# LEDS3.net
KiCad netlist of a schematic drawn in Altium Designer
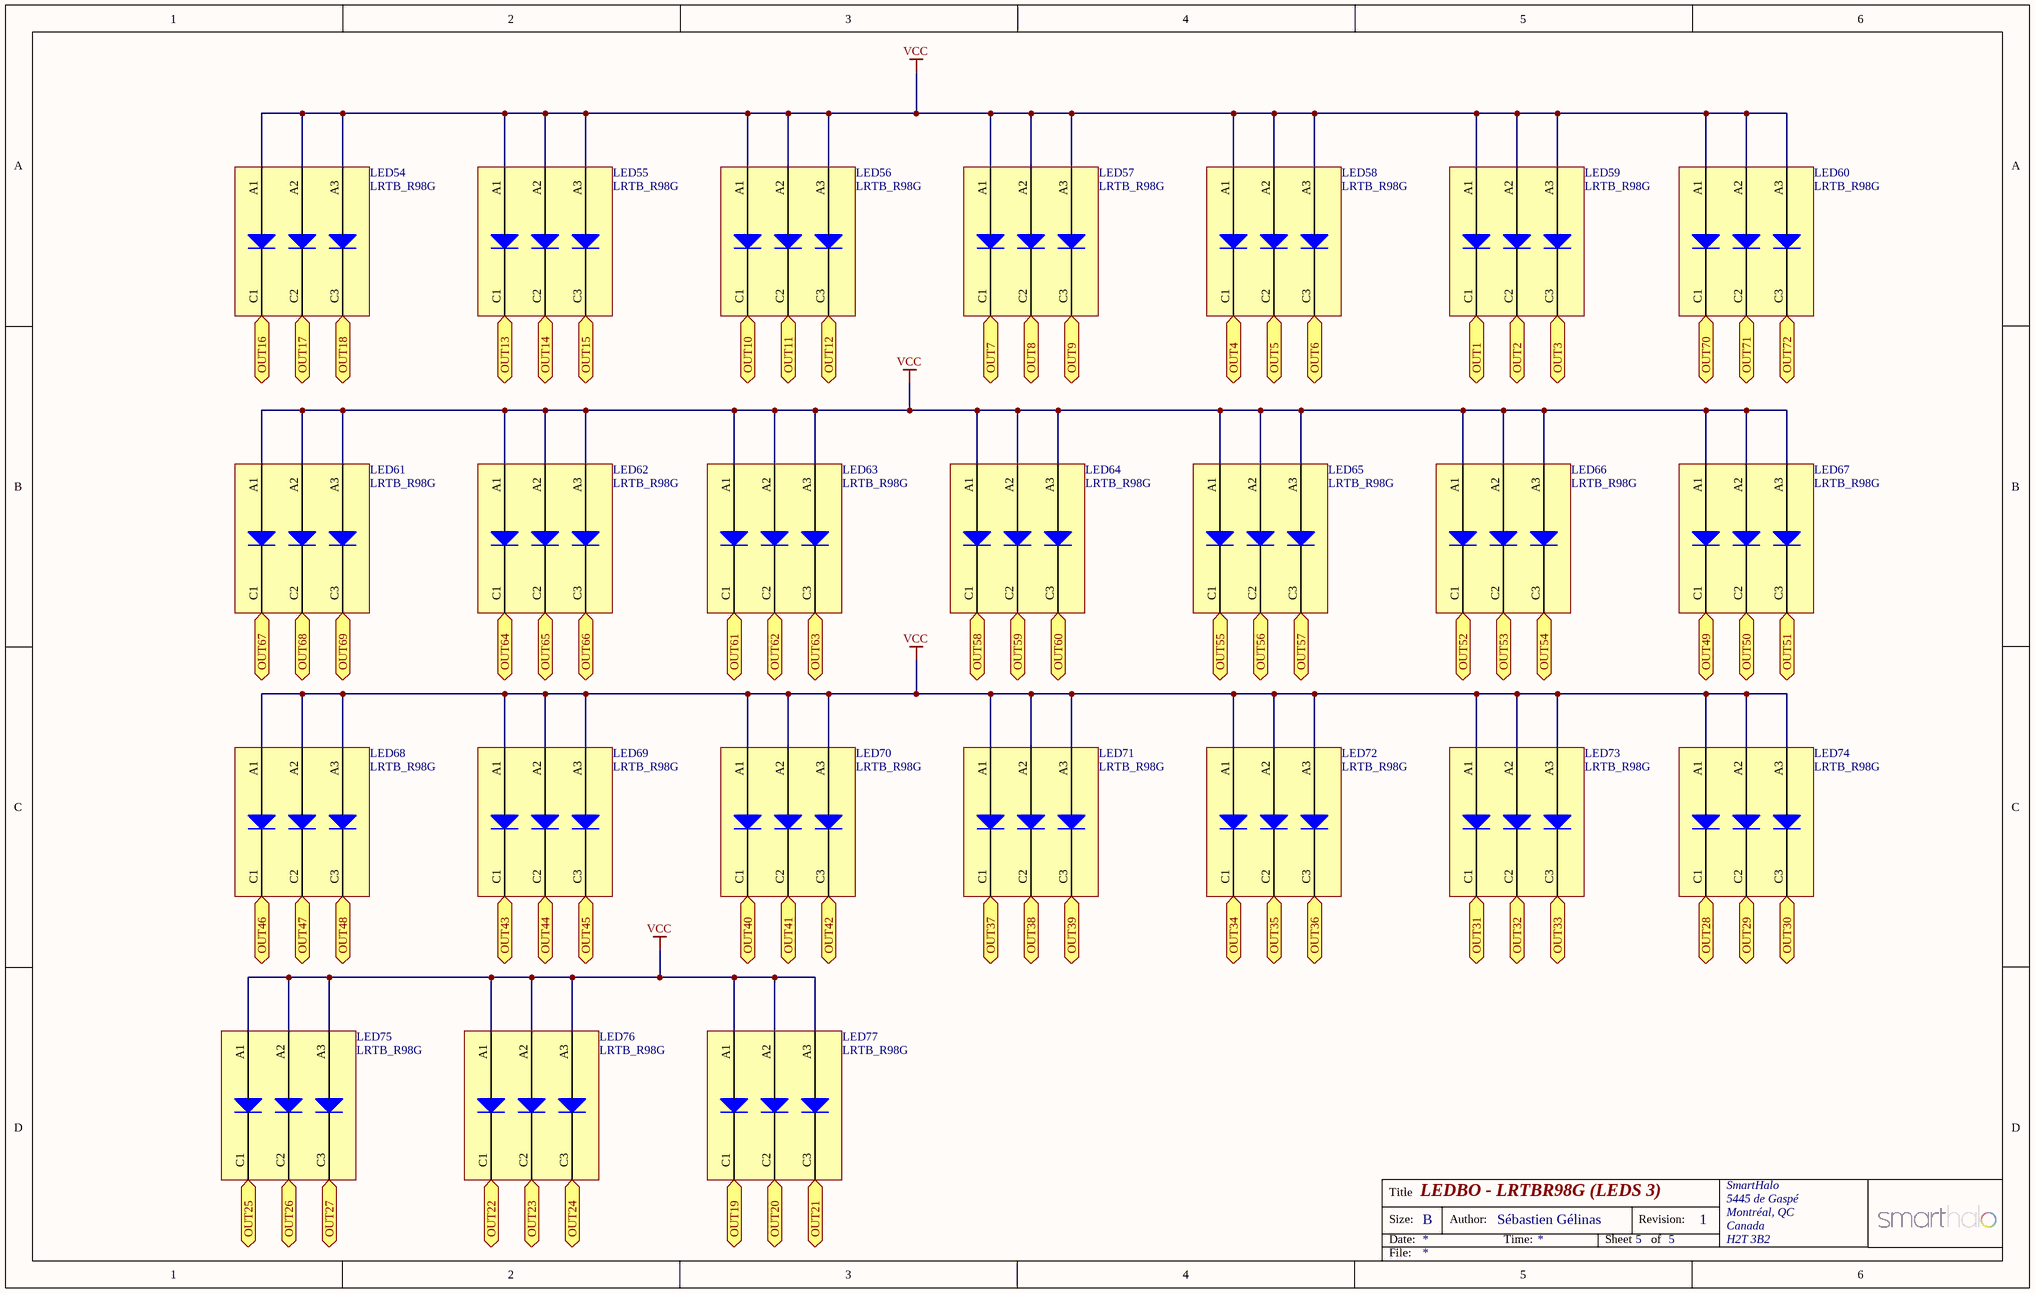
[diagram p0: LEDS3.SchDoc]

(export (version "E")
  (design (tool "Eeschema 10.0.6"))
  (components
    (comp (ref "LED54")
      (value "LRTB_R98G")
      (footprint "LRTB_R98G")
      (description "IC RGB LED OSRAM")
      (fields (field (name "MANUFACTURER") "OSRAM"))
      (libsource (lib "SmartHalo_Symbols") (part "LRTB_R98G"))
    )
    (comp (ref "LED55")
      (value "LRTB_R98G")
      (footprint "LRTB_R98G")
      (description "IC RGB LED OSRAM")
      (fields (field (name "MANUFACTURER") "OSRAM"))
      (libsource (lib "SmartHalo_Symbols") (part "LRTB_R98G"))
    )
    (comp (ref "LED56")
      (value "LRTB_R98G")
      (footprint "LRTB_R98G")
      (description "IC RGB LED OSRAM")
      (fields (field (name "MANUFACTURER") "OSRAM"))
      (libsource (lib "SmartHalo_Symbols") (part "LRTB_R98G"))
    )
    (comp (ref "LED57")
      (value "LRTB_R98G")
      (footprint "LRTB_R98G")
      (description "IC RGB LED OSRAM")
      (fields (field (name "MANUFACTURER") "OSRAM"))
      (libsource (lib "SmartHalo_Symbols") (part "LRTB_R98G"))
    )
    (comp (ref "LED58")
      (value "LRTB_R98G")
      (footprint "LRTB_R98G")
      (description "IC RGB LED OSRAM")
      (fields (field (name "MANUFACTURER") "OSRAM"))
      (libsource (lib "SmartHalo_Symbols") (part "LRTB_R98G"))
    )
    (comp (ref "LED59")
      (value "LRTB_R98G")
      (footprint "LRTB_R98G")
      (description "IC RGB LED OSRAM")
      (fields (field (name "MANUFACTURER") "OSRAM"))
      (libsource (lib "SmartHalo_Symbols") (part "LRTB_R98G"))
    )
    (comp (ref "LED60")
      (value "LRTB_R98G")
      (footprint "LRTB_R98G")
      (description "IC RGB LED OSRAM")
      (fields (field (name "MANUFACTURER") "OSRAM"))
      (libsource (lib "SmartHalo_Symbols") (part "LRTB_R98G"))
    )
    (comp (ref "LED61")
      (value "LRTB_R98G")
      (footprint "LRTB_R98G")
      (description "IC RGB LED OSRAM")
      (fields (field (name "MANUFACTURER") "OSRAM"))
      (libsource (lib "SmartHalo_Symbols") (part "LRTB_R98G"))
    )
    (comp (ref "LED62")
      (value "LRTB_R98G")
      (footprint "LRTB_R98G")
      (description "IC RGB LED OSRAM")
      (fields (field (name "MANUFACTURER") "OSRAM"))
      (libsource (lib "SmartHalo_Symbols") (part "LRTB_R98G"))
    )
    (comp (ref "LED63")
      (value "LRTB_R98G")
      (footprint "LRTB_R98G")
      (description "IC RGB LED OSRAM")
      (fields (field (name "MANUFACTURER") "OSRAM"))
      (libsource (lib "SmartHalo_Symbols") (part "LRTB_R98G"))
    )
    (comp (ref "LED64")
      (value "LRTB_R98G")
      (footprint "LRTB_R98G")
      (description "IC RGB LED OSRAM")
      (fields (field (name "MANUFACTURER") "OSRAM"))
      (libsource (lib "SmartHalo_Symbols") (part "LRTB_R98G"))
    )
    (comp (ref "LED65")
      (value "LRTB_R98G")
      (footprint "LRTB_R98G")
      (description "IC RGB LED OSRAM")
      (fields (field (name "MANUFACTURER") "OSRAM"))
      (libsource (lib "SmartHalo_Symbols") (part "LRTB_R98G"))
    )
    (comp (ref "LED66")
      (value "LRTB_R98G")
      (footprint "LRTB_R98G")
      (description "IC RGB LED OSRAM")
      (fields (field (name "MANUFACTURER") "OSRAM"))
      (libsource (lib "SmartHalo_Symbols") (part "LRTB_R98G"))
    )
    (comp (ref "LED67")
      (value "LRTB_R98G")
      (footprint "LRTB_R98G")
      (description "IC RGB LED OSRAM")
      (fields (field (name "MANUFACTURER") "OSRAM"))
      (libsource (lib "SmartHalo_Symbols") (part "LRTB_R98G"))
    )
    (comp (ref "LED68")
      (value "LRTB_R98G")
      (footprint "LRTB_R98G")
      (description "IC RGB LED OSRAM")
      (fields (field (name "MANUFACTURER") "OSRAM"))
      (libsource (lib "SmartHalo_Symbols") (part "LRTB_R98G"))
    )
    (comp (ref "LED69")
      (value "LRTB_R98G")
      (footprint "LRTB_R98G")
      (description "IC RGB LED OSRAM")
      (fields (field (name "MANUFACTURER") "OSRAM"))
      (libsource (lib "SmartHalo_Symbols") (part "LRTB_R98G"))
    )
    (comp (ref "LED70")
      (value "LRTB_R98G")
      (footprint "LRTB_R98G")
      (description "IC RGB LED OSRAM")
      (fields (field (name "MANUFACTURER") "OSRAM"))
      (libsource (lib "SmartHalo_Symbols") (part "LRTB_R98G"))
    )
    (comp (ref "LED71")
      (value "LRTB_R98G")
      (footprint "LRTB_R98G")
      (description "IC RGB LED OSRAM")
      (fields (field (name "MANUFACTURER") "OSRAM"))
      (libsource (lib "SmartHalo_Symbols") (part "LRTB_R98G"))
    )
    (comp (ref "LED72")
      (value "LRTB_R98G")
      (footprint "LRTB_R98G")
      (description "IC RGB LED OSRAM")
      (fields (field (name "MANUFACTURER") "OSRAM"))
      (libsource (lib "SmartHalo_Symbols") (part "LRTB_R98G"))
    )
    (comp (ref "LED73")
      (value "LRTB_R98G")
      (footprint "LRTB_R98G")
      (description "IC RGB LED OSRAM")
      (fields (field (name "MANUFACTURER") "OSRAM"))
      (libsource (lib "SmartHalo_Symbols") (part "LRTB_R98G"))
    )
    (comp (ref "LED74")
      (value "LRTB_R98G")
      (footprint "LRTB_R98G")
      (description "IC RGB LED OSRAM")
      (fields (field (name "MANUFACTURER") "OSRAM"))
      (libsource (lib "SmartHalo_Symbols") (part "LRTB_R98G"))
    )
    (comp (ref "LED75")
      (value "LRTB_R98G")
      (footprint "LRTB_R98G")
      (description "IC RGB LED OSRAM")
      (fields (field (name "MANUFACTURER") "OSRAM"))
      (libsource (lib "SmartHalo_Symbols") (part "LRTB_R98G"))
    )
    (comp (ref "LED76")
      (value "LRTB_R98G")
      (footprint "LRTB_R98G")
      (description "IC RGB LED OSRAM")
      (fields (field (name "MANUFACTURER") "OSRAM"))
      (libsource (lib "SmartHalo_Symbols") (part "LRTB_R98G"))
    )
    (comp (ref "LED77")
      (value "LRTB_R98G")
      (footprint "LRTB_R98G")
      (description "IC RGB LED OSRAM")
      (fields (field (name "MANUFACTURER") "OSRAM"))
      (libsource (lib "SmartHalo_Symbols") (part "LRTB_R98G"))
    )
  )
  (nets
    (net (code "1") (name "/OUT1") (class "Default")
      (node (ref "LED59") (pin "C1") (pinfunction "Cathode_Blue_C1") (pintype "passive"))
    )
    (net (code "2") (name "/OUT2") (class "Default")
      (node (ref "LED59") (pin "C2") (pinfunction "Cathode_Green_C2") (pintype "passive"))
    )
    (net (code "3") (name "/OUT3") (class "Default")
      (node (ref "LED59") (pin "C3") (pinfunction "Cathode_Red_C3") (pintype "passive"))
    )
    (net (code "4") (name "/OUT4") (class "Default")
      (node (ref "LED58") (pin "C1") (pinfunction "Cathode_Blue_C1") (pintype "passive"))
    )
    (net (code "5") (name "/OUT5") (class "Default")
      (node (ref "LED58") (pin "C2") (pinfunction "Cathode_Green_C2") (pintype "passive"))
    )
    (net (code "6") (name "/OUT6") (class "Default")
      (node (ref "LED58") (pin "C3") (pinfunction "Cathode_Red_C3") (pintype "passive"))
    )
    (net (code "7") (name "/OUT7") (class "Default")
      (node (ref "LED57") (pin "C1") (pinfunction "Cathode_Blue_C1") (pintype "passive"))
    )
    (net (code "8") (name "/OUT8") (class "Default")
      (node (ref "LED57") (pin "C2") (pinfunction "Cathode_Green_C2") (pintype "passive"))
    )
    (net (code "9") (name "/OUT9") (class "Default")
      (node (ref "LED57") (pin "C3") (pinfunction "Cathode_Red_C3") (pintype "passive"))
    )
    (net (code "10") (name "/OUT10") (class "Default")
      (node (ref "LED56") (pin "C1") (pinfunction "Cathode_Blue_C1") (pintype "passive"))
    )
    (net (code "11") (name "/OUT11") (class "Default")
      (node (ref "LED56") (pin "C2") (pinfunction "Cathode_Green_C2") (pintype "passive"))
    )
    (net (code "12") (name "/OUT12") (class "Default")
      (node (ref "LED56") (pin "C3") (pinfunction "Cathode_Red_C3") (pintype "passive"))
    )
    (net (code "13") (name "/OUT13") (class "Default")
      (node (ref "LED55") (pin "C1") (pinfunction "Cathode_Blue_C1") (pintype "passive"))
    )
    (net (code "14") (name "/OUT14") (class "Default")
      (node (ref "LED55") (pin "C2") (pinfunction "Cathode_Green_C2") (pintype "passive"))
    )
    (net (code "15") (name "/OUT15") (class "Default")
      (node (ref "LED55") (pin "C3") (pinfunction "Cathode_Red_C3") (pintype "passive"))
    )
    (net (code "16") (name "/OUT16") (class "Default")
      (node (ref "LED54") (pin "C1") (pinfunction "Cathode_Blue_C1") (pintype "passive"))
    )
    (net (code "17") (name "/OUT17") (class "Default")
      (node (ref "LED54") (pin "C2") (pinfunction "Cathode_Green_C2") (pintype "passive"))
    )
    (net (code "18") (name "/OUT18") (class "Default")
      (node (ref "LED54") (pin "C3") (pinfunction "Cathode_Red_C3") (pintype "passive"))
    )
    (net (code "19") (name "/OUT19") (class "Default")
      (node (ref "LED77") (pin "C1") (pinfunction "Cathode_Blue_C1") (pintype "passive"))
    )
    (net (code "20") (name "/OUT20") (class "Default")
      (node (ref "LED77") (pin "C2") (pinfunction "Cathode_Green_C2") (pintype "passive"))
    )
    (net (code "21") (name "/OUT21") (class "Default")
      (node (ref "LED77") (pin "C3") (pinfunction "Cathode_Red_C3") (pintype "passive"))
    )
    (net (code "22") (name "/OUT22") (class "Default")
      (node (ref "LED76") (pin "C1") (pinfunction "Cathode_Blue_C1") (pintype "passive"))
    )
    (net (code "23") (name "/OUT23") (class "Default")
      (node (ref "LED76") (pin "C2") (pinfunction "Cathode_Green_C2") (pintype "passive"))
    )
    (net (code "24") (name "/OUT24") (class "Default")
      (node (ref "LED76") (pin "C3") (pinfunction "Cathode_Red_C3") (pintype "passive"))
    )
    (net (code "25") (name "/OUT25") (class "Default")
      (node (ref "LED75") (pin "C1") (pinfunction "Cathode_Blue_C1") (pintype "passive"))
    )
    (net (code "26") (name "/OUT26") (class "Default")
      (node (ref "LED75") (pin "C2") (pinfunction "Cathode_Green_C2") (pintype "passive"))
    )
    (net (code "27") (name "/OUT27") (class "Default")
      (node (ref "LED75") (pin "C3") (pinfunction "Cathode_Red_C3") (pintype "passive"))
    )
    (net (code "28") (name "/OUT28") (class "Default")
      (node (ref "LED74") (pin "C1") (pinfunction "Cathode_Blue_C1") (pintype "passive"))
    )
    (net (code "29") (name "/OUT29") (class "Default")
      (node (ref "LED74") (pin "C2") (pinfunction "Cathode_Green_C2") (pintype "passive"))
    )
    (net (code "30") (name "/OUT30") (class "Default")
      (node (ref "LED74") (pin "C3") (pinfunction "Cathode_Red_C3") (pintype "passive"))
    )
    (net (code "31") (name "/OUT31") (class "Default")
      (node (ref "LED73") (pin "C1") (pinfunction "Cathode_Blue_C1") (pintype "passive"))
    )
    (net (code "32") (name "/OUT32") (class "Default")
      (node (ref "LED73") (pin "C2") (pinfunction "Cathode_Green_C2") (pintype "passive"))
    )
    (net (code "33") (name "/OUT33") (class "Default")
      (node (ref "LED73") (pin "C3") (pinfunction "Cathode_Red_C3") (pintype "passive"))
    )
    (net (code "34") (name "/OUT34") (class "Default")
      (node (ref "LED72") (pin "C1") (pinfunction "Cathode_Blue_C1") (pintype "passive"))
    )
    (net (code "35") (name "/OUT35") (class "Default")
      (node (ref "LED72") (pin "C2") (pinfunction "Cathode_Green_C2") (pintype "passive"))
    )
    (net (code "36") (name "/OUT36") (class "Default")
      (node (ref "LED72") (pin "C3") (pinfunction "Cathode_Red_C3") (pintype "passive"))
    )
    (net (code "37") (name "/OUT37") (class "Default")
      (node (ref "LED71") (pin "C1") (pinfunction "Cathode_Blue_C1") (pintype "passive"))
    )
    (net (code "38") (name "/OUT38") (class "Default")
      (node (ref "LED71") (pin "C2") (pinfunction "Cathode_Green_C2") (pintype "passive"))
    )
    (net (code "39") (name "/OUT39") (class "Default")
      (node (ref "LED71") (pin "C3") (pinfunction "Cathode_Red_C3") (pintype "passive"))
    )
    (net (code "40") (name "/OUT40") (class "Default")
      (node (ref "LED70") (pin "C1") (pinfunction "Cathode_Blue_C1") (pintype "passive"))
    )
    (net (code "41") (name "/OUT41") (class "Default")
      (node (ref "LED70") (pin "C2") (pinfunction "Cathode_Green_C2") (pintype "passive"))
    )
    (net (code "42") (name "/OUT42") (class "Default")
      (node (ref "LED70") (pin "C3") (pinfunction "Cathode_Red_C3") (pintype "passive"))
    )
    (net (code "43") (name "/OUT43") (class "Default")
      (node (ref "LED69") (pin "C1") (pinfunction "Cathode_Blue_C1") (pintype "passive"))
    )
    (net (code "44") (name "/OUT44") (class "Default")
      (node (ref "LED69") (pin "C2") (pinfunction "Cathode_Green_C2") (pintype "passive"))
    )
    (net (code "45") (name "/OUT45") (class "Default")
      (node (ref "LED69") (pin "C3") (pinfunction "Cathode_Red_C3") (pintype "passive"))
    )
    (net (code "46") (name "/OUT46") (class "Default")
      (node (ref "LED68") (pin "C1") (pinfunction "Cathode_Blue_C1") (pintype "passive"))
    )
    (net (code "47") (name "/OUT47") (class "Default")
      (node (ref "LED68") (pin "C2") (pinfunction "Cathode_Green_C2") (pintype "passive"))
    )
    (net (code "48") (name "/OUT48") (class "Default")
      (node (ref "LED68") (pin "C3") (pinfunction "Cathode_Red_C3") (pintype "passive"))
    )
    (net (code "49") (name "/OUT49") (class "Default")
      (node (ref "LED67") (pin "C1") (pinfunction "Cathode_Blue_C1") (pintype "passive"))
    )
    (net (code "50") (name "/OUT50") (class "Default")
      (node (ref "LED67") (pin "C2") (pinfunction "Cathode_Green_C2") (pintype "passive"))
    )
    (net (code "51") (name "/OUT51") (class "Default")
      (node (ref "LED67") (pin "C3") (pinfunction "Cathode_Red_C3") (pintype "passive"))
    )
    (net (code "52") (name "/OUT52") (class "Default")
      (node (ref "LED66") (pin "C1") (pinfunction "Cathode_Blue_C1") (pintype "passive"))
    )
    (net (code "53") (name "/OUT53") (class "Default")
      (node (ref "LED66") (pin "C2") (pinfunction "Cathode_Green_C2") (pintype "passive"))
    )
    (net (code "54") (name "/OUT54") (class "Default")
      (node (ref "LED66") (pin "C3") (pinfunction "Cathode_Red_C3") (pintype "passive"))
    )
    (net (code "55") (name "/OUT55") (class "Default")
      (node (ref "LED65") (pin "C1") (pinfunction "Cathode_Blue_C1") (pintype "passive"))
    )
    (net (code "56") (name "/OUT56") (class "Default")
      (node (ref "LED65") (pin "C2") (pinfunction "Cathode_Green_C2") (pintype "passive"))
    )
    (net (code "57") (name "/OUT57") (class "Default")
      (node (ref "LED65") (pin "C3") (pinfunction "Cathode_Red_C3") (pintype "passive"))
    )
    (net (code "58") (name "/OUT58") (class "Default")
      (node (ref "LED64") (pin "C1") (pinfunction "Cathode_Blue_C1") (pintype "passive"))
    )
    (net (code "59") (name "/OUT59") (class "Default")
      (node (ref "LED64") (pin "C2") (pinfunction "Cathode_Green_C2") (pintype "passive"))
    )
    (net (code "60") (name "/OUT60") (class "Default")
      (node (ref "LED64") (pin "C3") (pinfunction "Cathode_Red_C3") (pintype "passive"))
    )
    (net (code "61") (name "/OUT61") (class "Default")
      (node (ref "LED63") (pin "C1") (pinfunction "Cathode_Blue_C1") (pintype "passive"))
    )
    (net (code "62") (name "/OUT62") (class "Default")
      (node (ref "LED63") (pin "C2") (pinfunction "Cathode_Green_C2") (pintype "passive"))
    )
    (net (code "63") (name "/OUT63") (class "Default")
      (node (ref "LED63") (pin "C3") (pinfunction "Cathode_Red_C3") (pintype "passive"))
    )
    (net (code "64") (name "/OUT64") (class "Default")
      (node (ref "LED62") (pin "C1") (pinfunction "Cathode_Blue_C1") (pintype "passive"))
    )
    (net (code "65") (name "/OUT65") (class "Default")
      (node (ref "LED62") (pin "C2") (pinfunction "Cathode_Green_C2") (pintype "passive"))
    )
    (net (code "66") (name "/OUT66") (class "Default")
      (node (ref "LED62") (pin "C3") (pinfunction "Cathode_Red_C3") (pintype "passive"))
    )
    (net (code "67") (name "/OUT67") (class "Default")
      (node (ref "LED61") (pin "C1") (pinfunction "Cathode_Blue_C1") (pintype "passive"))
    )
    (net (code "68") (name "/OUT68") (class "Default")
      (node (ref "LED61") (pin "C2") (pinfunction "Cathode_Green_C2") (pintype "passive"))
    )
    (net (code "69") (name "/OUT69") (class "Default")
      (node (ref "LED61") (pin "C3") (pinfunction "Cathode_Red_C3") (pintype "passive"))
    )
    (net (code "70") (name "/OUT70") (class "Default")
      (node (ref "LED60") (pin "C1") (pinfunction "Cathode_Blue_C1") (pintype "passive"))
    )
    (net (code "71") (name "/OUT71") (class "Default")
      (node (ref "LED60") (pin "C2") (pinfunction "Cathode_Green_C2") (pintype "passive"))
    )
    (net (code "72") (name "/OUT72") (class "Default")
      (node (ref "LED60") (pin "C3") (pinfunction "Cathode_Red_C3") (pintype "passive"))
    )
    (net (code "73") (name "VCC") (class "Default")
      (node (ref "LED54") (pin "A1") (pinfunction "Anode_Blue_A1") (pintype "passive"))
      (node (ref "LED54") (pin "A2") (pinfunction "Anode_Green_A2") (pintype "passive"))
      (node (ref "LED54") (pin "A3") (pinfunction "Anode_Red_A3") (pintype "passive"))
      (node (ref "LED55") (pin "A1") (pinfunction "Anode_Blue_A1") (pintype "passive"))
      (node (ref "LED55") (pin "A2") (pinfunction "Anode_Green_A2") (pintype "passive"))
      (node (ref "LED55") (pin "A3") (pinfunction "Anode_Red_A3") (pintype "passive"))
      (node (ref "LED56") (pin "A1") (pinfunction "Anode_Blue_A1") (pintype "passive"))
      (node (ref "LED56") (pin "A2") (pinfunction "Anode_Green_A2") (pintype "passive"))
      (node (ref "LED56") (pin "A3") (pinfunction "Anode_Red_A3") (pintype "passive"))
      (node (ref "LED57") (pin "A1") (pinfunction "Anode_Blue_A1") (pintype "passive"))
      (node (ref "LED57") (pin "A2") (pinfunction "Anode_Green_A2") (pintype "passive"))
      (node (ref "LED57") (pin "A3") (pinfunction "Anode_Red_A3") (pintype "passive"))
      (node (ref "LED58") (pin "A1") (pinfunction "Anode_Blue_A1") (pintype "passive"))
      (node (ref "LED58") (pin "A2") (pinfunction "Anode_Green_A2") (pintype "passive"))
      (node (ref "LED58") (pin "A3") (pinfunction "Anode_Red_A3") (pintype "passive"))
      (node (ref "LED59") (pin "A1") (pinfunction "Anode_Blue_A1") (pintype "passive"))
      (node (ref "LED59") (pin "A2") (pinfunction "Anode_Green_A2") (pintype "passive"))
      (node (ref "LED59") (pin "A3") (pinfunction "Anode_Red_A3") (pintype "passive"))
      (node (ref "LED60") (pin "A1") (pinfunction "Anode_Blue_A1") (pintype "passive"))
      (node (ref "LED60") (pin "A2") (pinfunction "Anode_Green_A2") (pintype "passive"))
      (node (ref "LED60") (pin "A3") (pinfunction "Anode_Red_A3") (pintype "passive"))
      (node (ref "LED61") (pin "A1") (pinfunction "Anode_Blue_A1") (pintype "passive"))
      (node (ref "LED61") (pin "A2") (pinfunction "Anode_Green_A2") (pintype "passive"))
      (node (ref "LED61") (pin "A3") (pinfunction "Anode_Red_A3") (pintype "passive"))
      (node (ref "LED62") (pin "A1") (pinfunction "Anode_Blue_A1") (pintype "passive"))
      (node (ref "LED62") (pin "A2") (pinfunction "Anode_Green_A2") (pintype "passive"))
      (node (ref "LED62") (pin "A3") (pinfunction "Anode_Red_A3") (pintype "passive"))
      (node (ref "LED63") (pin "A1") (pinfunction "Anode_Blue_A1") (pintype "passive"))
      (node (ref "LED63") (pin "A2") (pinfunction "Anode_Green_A2") (pintype "passive"))
      (node (ref "LED63") (pin "A3") (pinfunction "Anode_Red_A3") (pintype "passive"))
      (node (ref "LED64") (pin "A1") (pinfunction "Anode_Blue_A1") (pintype "passive"))
      (node (ref "LED64") (pin "A2") (pinfunction "Anode_Green_A2") (pintype "passive"))
      (node (ref "LED64") (pin "A3") (pinfunction "Anode_Red_A3") (pintype "passive"))
      (node (ref "LED65") (pin "A1") (pinfunction "Anode_Blue_A1") (pintype "passive"))
      (node (ref "LED65") (pin "A2") (pinfunction "Anode_Green_A2") (pintype "passive"))
      (node (ref "LED65") (pin "A3") (pinfunction "Anode_Red_A3") (pintype "passive"))
      (node (ref "LED66") (pin "A1") (pinfunction "Anode_Blue_A1") (pintype "passive"))
      (node (ref "LED66") (pin "A2") (pinfunction "Anode_Green_A2") (pintype "passive"))
      (node (ref "LED66") (pin "A3") (pinfunction "Anode_Red_A3") (pintype "passive"))
      (node (ref "LED67") (pin "A1") (pinfunction "Anode_Blue_A1") (pintype "passive"))
      (node (ref "LED67") (pin "A2") (pinfunction "Anode_Green_A2") (pintype "passive"))
      (node (ref "LED67") (pin "A3") (pinfunction "Anode_Red_A3") (pintype "passive"))
      (node (ref "LED68") (pin "A1") (pinfunction "Anode_Blue_A1") (pintype "passive"))
      (node (ref "LED68") (pin "A2") (pinfunction "Anode_Green_A2") (pintype "passive"))
      (node (ref "LED68") (pin "A3") (pinfunction "Anode_Red_A3") (pintype "passive"))
      (node (ref "LED69") (pin "A1") (pinfunction "Anode_Blue_A1") (pintype "passive"))
      (node (ref "LED69") (pin "A2") (pinfunction "Anode_Green_A2") (pintype "passive"))
      (node (ref "LED69") (pin "A3") (pinfunction "Anode_Red_A3") (pintype "passive"))
      (node (ref "LED70") (pin "A1") (pinfunction "Anode_Blue_A1") (pintype "passive"))
      (node (ref "LED70") (pin "A2") (pinfunction "Anode_Green_A2") (pintype "passive"))
      (node (ref "LED70") (pin "A3") (pinfunction "Anode_Red_A3") (pintype "passive"))
      (node (ref "LED71") (pin "A1") (pinfunction "Anode_Blue_A1") (pintype "passive"))
      (node (ref "LED71") (pin "A2") (pinfunction "Anode_Green_A2") (pintype "passive"))
      (node (ref "LED71") (pin "A3") (pinfunction "Anode_Red_A3") (pintype "passive"))
      (node (ref "LED72") (pin "A1") (pinfunction "Anode_Blue_A1") (pintype "passive"))
      (node (ref "LED72") (pin "A2") (pinfunction "Anode_Green_A2") (pintype "passive"))
      (node (ref "LED72") (pin "A3") (pinfunction "Anode_Red_A3") (pintype "passive"))
      (node (ref "LED73") (pin "A1") (pinfunction "Anode_Blue_A1") (pintype "passive"))
      (node (ref "LED73") (pin "A2") (pinfunction "Anode_Green_A2") (pintype "passive"))
      (node (ref "LED73") (pin "A3") (pinfunction "Anode_Red_A3") (pintype "passive"))
      (node (ref "LED74") (pin "A1") (pinfunction "Anode_Blue_A1") (pintype "passive"))
      (node (ref "LED74") (pin "A2") (pinfunction "Anode_Green_A2") (pintype "passive"))
      (node (ref "LED74") (pin "A3") (pinfunction "Anode_Red_A3") (pintype "passive"))
      (node (ref "LED75") (pin "A1") (pinfunction "Anode_Blue_A1") (pintype "passive"))
      (node (ref "LED75") (pin "A2") (pinfunction "Anode_Green_A2") (pintype "passive"))
      (node (ref "LED75") (pin "A3") (pinfunction "Anode_Red_A3") (pintype "passive"))
      (node (ref "LED76") (pin "A1") (pinfunction "Anode_Blue_A1") (pintype "passive"))
      (node (ref "LED76") (pin "A2") (pinfunction "Anode_Green_A2") (pintype "passive"))
      (node (ref "LED76") (pin "A3") (pinfunction "Anode_Red_A3") (pintype "passive"))
      (node (ref "LED77") (pin "A1") (pinfunction "Anode_Blue_A1") (pintype "passive"))
      (node (ref "LED77") (pin "A2") (pinfunction "Anode_Green_A2") (pintype "passive"))
      (node (ref "LED77") (pin "A3") (pinfunction "Anode_Red_A3") (pintype "passive"))
    )
  )
)
